# SG1000_-_SMS_OD.net
KiCad netlist of a schematic drawn in EAGLE
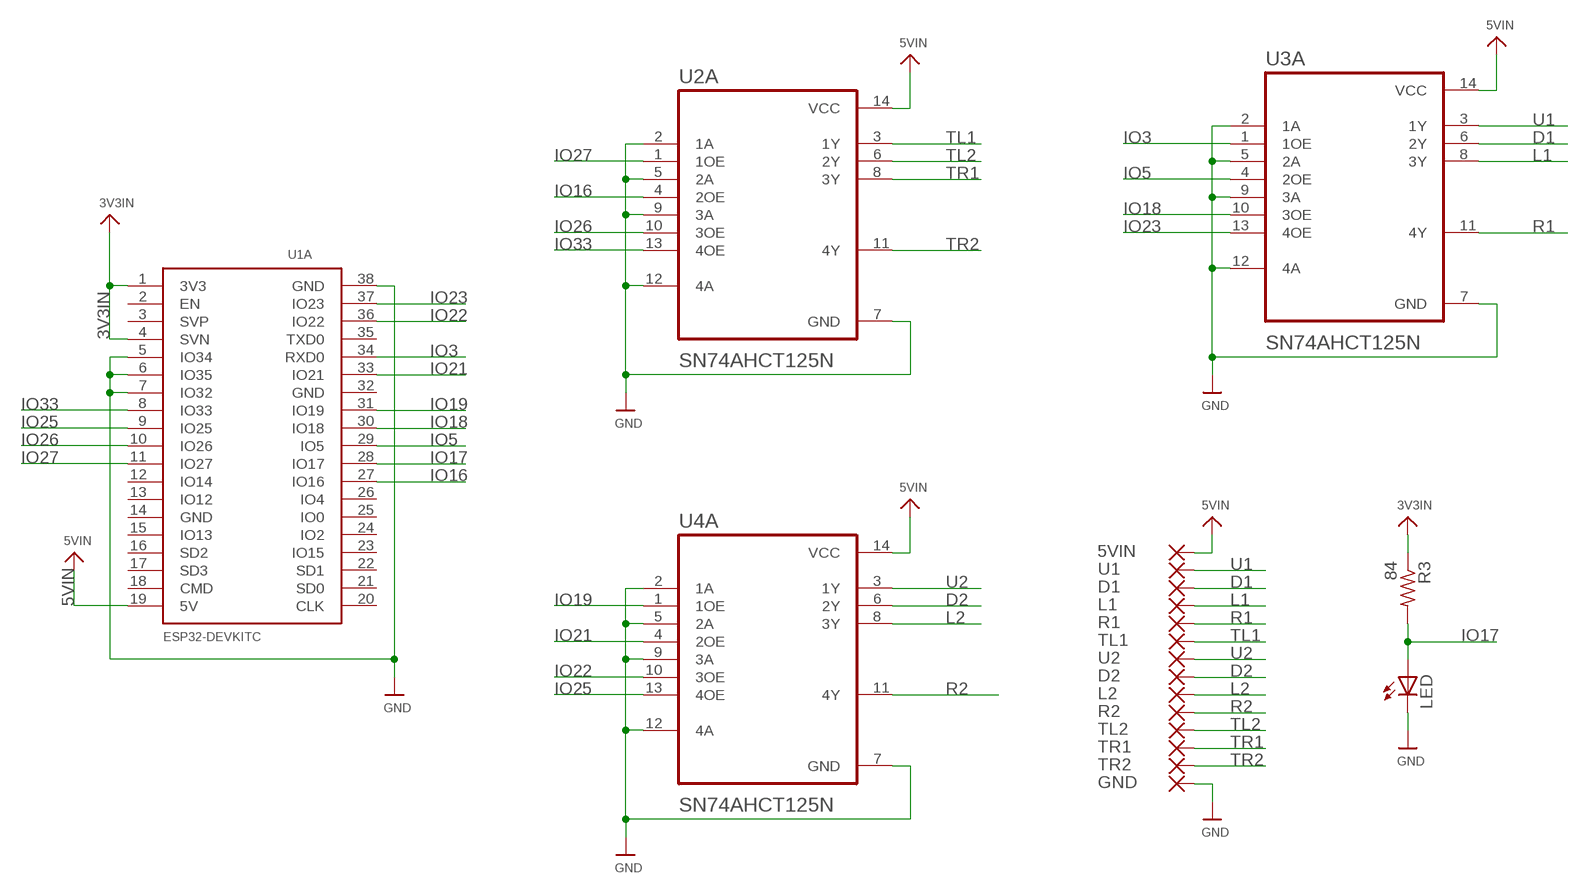
[diagram p0: schematic, sheet 1]

(export (version "E")
  (design (tool "Eeschema 10.0.6"))
  (components
    (comp (ref "5VIN")
      (value "SMD5")
      (footprint "eagle-import:SMD2,54-5,08")
      (libsource (lib "eagle-import") (part "SMD5"))
    )
    (comp (ref "D1")
      (value "SMD5")
      (footprint "eagle-import:SMD2,54-5,08")
      (libsource (lib "eagle-import") (part "SMD5"))
    )
    (comp (ref "D2")
      (value "SMD5")
      (footprint "eagle-import:SMD2,54-5,08")
      (libsource (lib "eagle-import") (part "SMD5"))
    )
    (comp (ref "GND")
      (value "SMD5")
      (footprint "eagle-import:SMD2,54-5,08")
      (libsource (lib "eagle-import") (part "SMD5"))
    )
    (comp (ref "L1")
      (value "SMD5")
      (footprint "eagle-import:SMD2,54-5,08")
      (libsource (lib "eagle-import") (part "SMD5"))
    )
    (comp (ref "L2")
      (value "SMD5")
      (footprint "eagle-import:SMD2,54-5,08")
      (libsource (lib "eagle-import") (part "SMD5"))
    )
    (comp (ref "LED")
      (value "LEDCHIPLED_1206")
      (footprint "eagle-import:CHIPLED_1206")
      (libsource (lib "eagle-import") (part "LEDCHIPLED_1206"))
    )
    (comp (ref "R1")
      (value "SMD5")
      (footprint "eagle-import:SMD2,54-5,08")
      (libsource (lib "eagle-import") (part "SMD5"))
    )
    (comp (ref "R2")
      (value "SMD5")
      (footprint "eagle-import:SMD2,54-5,08")
      (libsource (lib "eagle-import") (part "SMD5"))
    )
    (comp (ref "R3")
      (value "84")
      (footprint "eagle-import:R1206")
      (libsource (lib "eagle-import") (part "R-US_R1206"))
    )
    (comp (ref "TL1")
      (value "SMD5")
      (footprint "eagle-import:SMD2,54-5,08")
      (libsource (lib "eagle-import") (part "SMD5"))
    )
    (comp (ref "TL2")
      (value "SMD5")
      (footprint "eagle-import:SMD2,54-5,08")
      (libsource (lib "eagle-import") (part "SMD5"))
    )
    (comp (ref "TR1")
      (value "SMD5")
      (footprint "eagle-import:SMD2,54-5,08")
      (libsource (lib "eagle-import") (part "SMD5"))
    )
    (comp (ref "TR2")
      (value "SMD5")
      (footprint "eagle-import:SMD2,54-5,08")
      (libsource (lib "eagle-import") (part "SMD5"))
    )
    (comp (ref "U1")
      (value "SMD5")
      (footprint "eagle-import:SMD2,54-5,08")
      (libsource (lib "eagle-import") (part "SMD5"))
    )
    (comp (ref "U1A")
      (value "ESP32DEVKITC")
      (footprint "eagle-import:ESP32-DEVKITC")
      (libsource (lib "eagle-import") (part "ESP32DEVKITC"))
    )
    (comp (ref "U2")
      (value "SMD5")
      (footprint "eagle-import:SMD2,54-5,08")
      (libsource (lib "eagle-import") (part "SMD5"))
    )
    (comp (ref "U2A")
      (value "SN74AHCT125N")
      (footprint "eagle-import:DIP794W45P254L1969H508Q14")
      (fields (field (name "MF") "Texas Instruments"))
      (libsource (lib "eagle-import") (part "SN74AHCT125N"))
    )
    (comp (ref "U3A")
      (value "SN74AHCT125N")
      (footprint "eagle-import:DIP794W45P254L1969H508Q14")
      (fields (field (name "MF") "Texas Instruments"))
      (libsource (lib "eagle-import") (part "SN74AHCT125N"))
    )
    (comp (ref "U4A")
      (value "SN74AHCT125N")
      (footprint "eagle-import:DIP794W45P254L1969H508Q14")
      (fields (field (name "MF") "Texas Instruments"))
      (libsource (lib "eagle-import") (part "SN74AHCT125N"))
    )
  )
  (nets
    (net (code "1") (name "/D1") (class "Default")
      (node (ref "D1") (pin "1") (pinfunction "P_1") (pintype "passive"))
      (node (ref "U3A") (pin "6") (pinfunction "2Y_6") (pintype "output"))
    )
    (net (code "2") (name "/D2") (class "Default")
      (node (ref "D2") (pin "1") (pinfunction "P_1") (pintype "passive"))
      (node (ref "U4A") (pin "6") (pinfunction "2Y_6") (pintype "output"))
    )
    (net (code "3") (name "/IO3") (class "Default")
      (node (ref "U1A") (pin "34") (pinfunction "RXD0_34") (pintype "bidirectional"))
      (node (ref "U3A") (pin "1") (pinfunction "1OE_1") (pintype "input"))
    )
    (net (code "4") (name "/IO5") (class "Default")
      (node (ref "U1A") (pin "29") (pinfunction "IO5_29") (pintype "bidirectional"))
      (node (ref "U3A") (pin "4") (pinfunction "2OE_4") (pintype "input"))
    )
    (net (code "5") (name "/IO16") (class "Default")
      (node (ref "U1A") (pin "27") (pinfunction "IO16_27") (pintype "bidirectional"))
      (node (ref "U2A") (pin "4") (pinfunction "2OE_4") (pintype "input"))
    )
    (net (code "6") (name "/IO17") (class "Default")
      (node (ref "LED") (pin "A") (pinfunction "A_A") (pintype "passive"))
      (node (ref "R3") (pin "2") (pinfunction "2_2") (pintype "passive"))
      (node (ref "U1A") (pin "28") (pinfunction "IO17_28") (pintype "bidirectional"))
    )
    (net (code "7") (name "/IO18") (class "Default")
      (node (ref "U1A") (pin "30") (pinfunction "IO18_30") (pintype "bidirectional"))
      (node (ref "U3A") (pin "10") (pinfunction "3OE_10") (pintype "input"))
    )
    (net (code "8") (name "/IO19") (class "Default")
      (node (ref "U1A") (pin "31") (pinfunction "IO19_31") (pintype "bidirectional"))
      (node (ref "U4A") (pin "1") (pinfunction "1OE_1") (pintype "input"))
    )
    (net (code "9") (name "/IO21") (class "Default")
      (node (ref "U1A") (pin "33") (pinfunction "IO21_33") (pintype "bidirectional"))
      (node (ref "U4A") (pin "4") (pinfunction "2OE_4") (pintype "input"))
    )
    (net (code "10") (name "/IO22") (class "Default")
      (node (ref "U1A") (pin "36") (pinfunction "IO22_36") (pintype "bidirectional"))
      (node (ref "U4A") (pin "10") (pinfunction "3OE_10") (pintype "input"))
    )
    (net (code "11") (name "/IO23") (class "Default")
      (node (ref "U1A") (pin "37") (pinfunction "IO23_37") (pintype "bidirectional"))
      (node (ref "U3A") (pin "13") (pinfunction "4OE_13") (pintype "input"))
    )
    (net (code "12") (name "/IO25") (class "Default")
      (node (ref "U1A") (pin "9") (pinfunction "IO25_9") (pintype "bidirectional"))
      (node (ref "U4A") (pin "13") (pinfunction "4OE_13") (pintype "input"))
    )
    (net (code "13") (name "/IO26") (class "Default")
      (node (ref "U1A") (pin "10") (pinfunction "IO26_10") (pintype "bidirectional"))
      (node (ref "U2A") (pin "10") (pinfunction "3OE_10") (pintype "input"))
    )
    (net (code "14") (name "/IO27") (class "Default")
      (node (ref "U1A") (pin "11") (pinfunction "IO27_11") (pintype "bidirectional"))
      (node (ref "U2A") (pin "1") (pinfunction "1OE_1") (pintype "input"))
    )
    (net (code "15") (name "/IO33") (class "Default")
      (node (ref "U1A") (pin "8") (pinfunction "IO33_8") (pintype "bidirectional"))
      (node (ref "U2A") (pin "13") (pinfunction "4OE_13") (pintype "input"))
    )
    (net (code "16") (name "/L1") (class "Default")
      (node (ref "L1") (pin "1") (pinfunction "P_1") (pintype "passive"))
      (node (ref "U3A") (pin "8") (pinfunction "3Y_8") (pintype "output"))
    )
    (net (code "17") (name "/L2") (class "Default")
      (node (ref "L2") (pin "1") (pinfunction "P_1") (pintype "passive"))
      (node (ref "U4A") (pin "8") (pinfunction "3Y_8") (pintype "output"))
    )
    (net (code "18") (name "/R1") (class "Default")
      (node (ref "R1") (pin "1") (pinfunction "P_1") (pintype "passive"))
      (node (ref "U3A") (pin "11") (pinfunction "4Y_11") (pintype "output"))
    )
    (net (code "19") (name "/R2") (class "Default")
      (node (ref "R2") (pin "1") (pinfunction "P_1") (pintype "passive"))
      (node (ref "U4A") (pin "11") (pinfunction "4Y_11") (pintype "output"))
    )
    (net (code "20") (name "/TL1") (class "Default")
      (node (ref "TL1") (pin "1") (pinfunction "P_1") (pintype "passive"))
      (node (ref "U2A") (pin "3") (pinfunction "1Y_3") (pintype "output"))
    )
    (net (code "21") (name "/TL2") (class "Default")
      (node (ref "TL2") (pin "1") (pinfunction "P_1") (pintype "passive"))
      (node (ref "U2A") (pin "6") (pinfunction "2Y_6") (pintype "output"))
    )
    (net (code "22") (name "/TR1") (class "Default")
      (node (ref "TR1") (pin "1") (pinfunction "P_1") (pintype "passive"))
      (node (ref "U2A") (pin "8") (pinfunction "3Y_8") (pintype "output"))
    )
    (net (code "23") (name "/TR2") (class "Default")
      (node (ref "TR2") (pin "1") (pinfunction "P_1") (pintype "passive"))
      (node (ref "U2A") (pin "11") (pinfunction "4Y_11") (pintype "output"))
    )
    (net (code "24") (name "/U1") (class "Default")
      (node (ref "U1") (pin "1") (pinfunction "P_1") (pintype "passive"))
      (node (ref "U3A") (pin "3") (pinfunction "1Y_3") (pintype "output"))
    )
    (net (code "25") (name "/U2") (class "Default")
      (node (ref "U2") (pin "1") (pinfunction "P_1") (pintype "passive"))
      (node (ref "U4A") (pin "3") (pinfunction "1Y_3") (pintype "output"))
    )
    (net (code "26") (name "3V3IN") (class "Default")
      (node (ref "R3") (pin "1") (pinfunction "1_1") (pintype "passive"))
      (node (ref "U1A") (pin "1") (pinfunction "3V3_1") (pintype "bidirectional"))
      (node (ref "U1A") (pin "4") (pinfunction "SVN_4") (pintype "bidirectional"))
    )
    (net (code "27") (name "5VIN") (class "Default")
      (node (ref "5VIN") (pin "1") (pinfunction "P_1") (pintype "passive"))
      (node (ref "U1A") (pin "19") (pinfunction "5V_19") (pintype "bidirectional"))
      (node (ref "U2A") (pin "14") (pinfunction "VCC_14") (pintype "power_in"))
      (node (ref "U3A") (pin "14") (pinfunction "VCC_14") (pintype "power_in"))
      (node (ref "U4A") (pin "14") (pinfunction "VCC_14") (pintype "power_in"))
    )
    (net (code "28") (name "GND") (class "Default")
      (node (ref "GND") (pin "1") (pinfunction "P_1") (pintype "passive"))
      (node (ref "LED") (pin "C") (pinfunction "C_C") (pintype "passive"))
      (node (ref "U1A") (pin "38") (pinfunction "GND_38") (pintype "bidirectional"))
      (node (ref "U1A") (pin "5") (pinfunction "IO34_5") (pintype "bidirectional"))
      (node (ref "U1A") (pin "6") (pinfunction "IO35_6") (pintype "bidirectional"))
      (node (ref "U1A") (pin "7") (pinfunction "IO32_7") (pintype "bidirectional"))
      (node (ref "U2A") (pin "12") (pinfunction "4A_12") (pintype "bidirectional"))
      (node (ref "U2A") (pin "2") (pinfunction "1A_2") (pintype "input"))
      (node (ref "U2A") (pin "5") (pinfunction "2A_5") (pintype "input"))
      (node (ref "U2A") (pin "7") (pinfunction "GND_7") (pintype "power_in"))
      (node (ref "U2A") (pin "9") (pinfunction "3A_9") (pintype "input"))
      (node (ref "U3A") (pin "12") (pinfunction "4A_12") (pintype "bidirectional"))
      (node (ref "U3A") (pin "2") (pinfunction "1A_2") (pintype "input"))
      (node (ref "U3A") (pin "5") (pinfunction "2A_5") (pintype "input"))
      (node (ref "U3A") (pin "7") (pinfunction "GND_7") (pintype "power_in"))
      (node (ref "U3A") (pin "9") (pinfunction "3A_9") (pintype "input"))
      (node (ref "U4A") (pin "12") (pinfunction "4A_12") (pintype "bidirectional"))
      (node (ref "U4A") (pin "2") (pinfunction "1A_2") (pintype "input"))
      (node (ref "U4A") (pin "5") (pinfunction "2A_5") (pintype "input"))
      (node (ref "U4A") (pin "7") (pinfunction "GND_7") (pintype "power_in"))
      (node (ref "U4A") (pin "9") (pinfunction "3A_9") (pintype "input"))
    )
    (net (code "29") (name "unconnected-(U1A-CLK-Pad20)") (class "Default")
      (node (ref "U1A") (pin "20") (pinfunction "CLK_20") (pintype "bidirectional"))
    )
    (net (code "30") (name "unconnected-(U1A-CMD-Pad18)") (class "Default")
      (node (ref "U1A") (pin "18") (pinfunction "CMD_18") (pintype "bidirectional"))
    )
    (net (code "31") (name "unconnected-(U1A-EN-Pad2)") (class "Default")
      (node (ref "U1A") (pin "2") (pinfunction "EN_2") (pintype "bidirectional"))
    )
    (net (code "32") (name "unconnected-(U1A-GND-Pad14)") (class "Default")
      (node (ref "U1A") (pin "14") (pinfunction "GND_14") (pintype "bidirectional"))
    )
    (net (code "33") (name "unconnected-(U1A-GND-Pad32)") (class "Default")
      (node (ref "U1A") (pin "32") (pinfunction "GND_32") (pintype "bidirectional"))
    )
    (net (code "34") (name "unconnected-(U1A-IO0-Pad25)") (class "Default")
      (node (ref "U1A") (pin "25") (pinfunction "IO0_25") (pintype "bidirectional"))
    )
    (net (code "35") (name "unconnected-(U1A-IO2-Pad24)") (class "Default")
      (node (ref "U1A") (pin "24") (pinfunction "IO2_24") (pintype "bidirectional"))
    )
    (net (code "36") (name "unconnected-(U1A-IO4-Pad26)") (class "Default")
      (node (ref "U1A") (pin "26") (pinfunction "IO4_26") (pintype "bidirectional"))
    )
    (net (code "37") (name "unconnected-(U1A-IO12-Pad13)") (class "Default")
      (node (ref "U1A") (pin "13") (pinfunction "IO12_13") (pintype "bidirectional"))
    )
    (net (code "38") (name "unconnected-(U1A-IO13-Pad15)") (class "Default")
      (node (ref "U1A") (pin "15") (pinfunction "IO13_15") (pintype "bidirectional"))
    )
    (net (code "39") (name "unconnected-(U1A-IO14-Pad12)") (class "Default")
      (node (ref "U1A") (pin "12") (pinfunction "IO14_12") (pintype "bidirectional"))
    )
    (net (code "40") (name "unconnected-(U1A-IO15-Pad23)") (class "Default")
      (node (ref "U1A") (pin "23") (pinfunction "IO15_23") (pintype "bidirectional"))
    )
    (net (code "41") (name "unconnected-(U1A-SD0-Pad21)") (class "Default")
      (node (ref "U1A") (pin "21") (pinfunction "SD0_21") (pintype "bidirectional"))
    )
    (net (code "42") (name "unconnected-(U1A-SD1-Pad22)") (class "Default")
      (node (ref "U1A") (pin "22") (pinfunction "SD1_22") (pintype "bidirectional"))
    )
    (net (code "43") (name "unconnected-(U1A-SD2-Pad16)") (class "Default")
      (node (ref "U1A") (pin "16") (pinfunction "SD2_16") (pintype "bidirectional"))
    )
    (net (code "44") (name "unconnected-(U1A-SD3-Pad17)") (class "Default")
      (node (ref "U1A") (pin "17") (pinfunction "SD3_17") (pintype "bidirectional"))
    )
    (net (code "45") (name "unconnected-(U1A-SVP-Pad3)") (class "Default")
      (node (ref "U1A") (pin "3") (pinfunction "SVP_3") (pintype "bidirectional"))
    )
    (net (code "46") (name "unconnected-(U1A-TXD0-Pad35)") (class "Default")
      (node (ref "U1A") (pin "35") (pinfunction "TXD0_35") (pintype "bidirectional"))
    )
  )
)
